# RLB_LTC5510.net
KiCad netlist of a schematic drawn in EAGLE
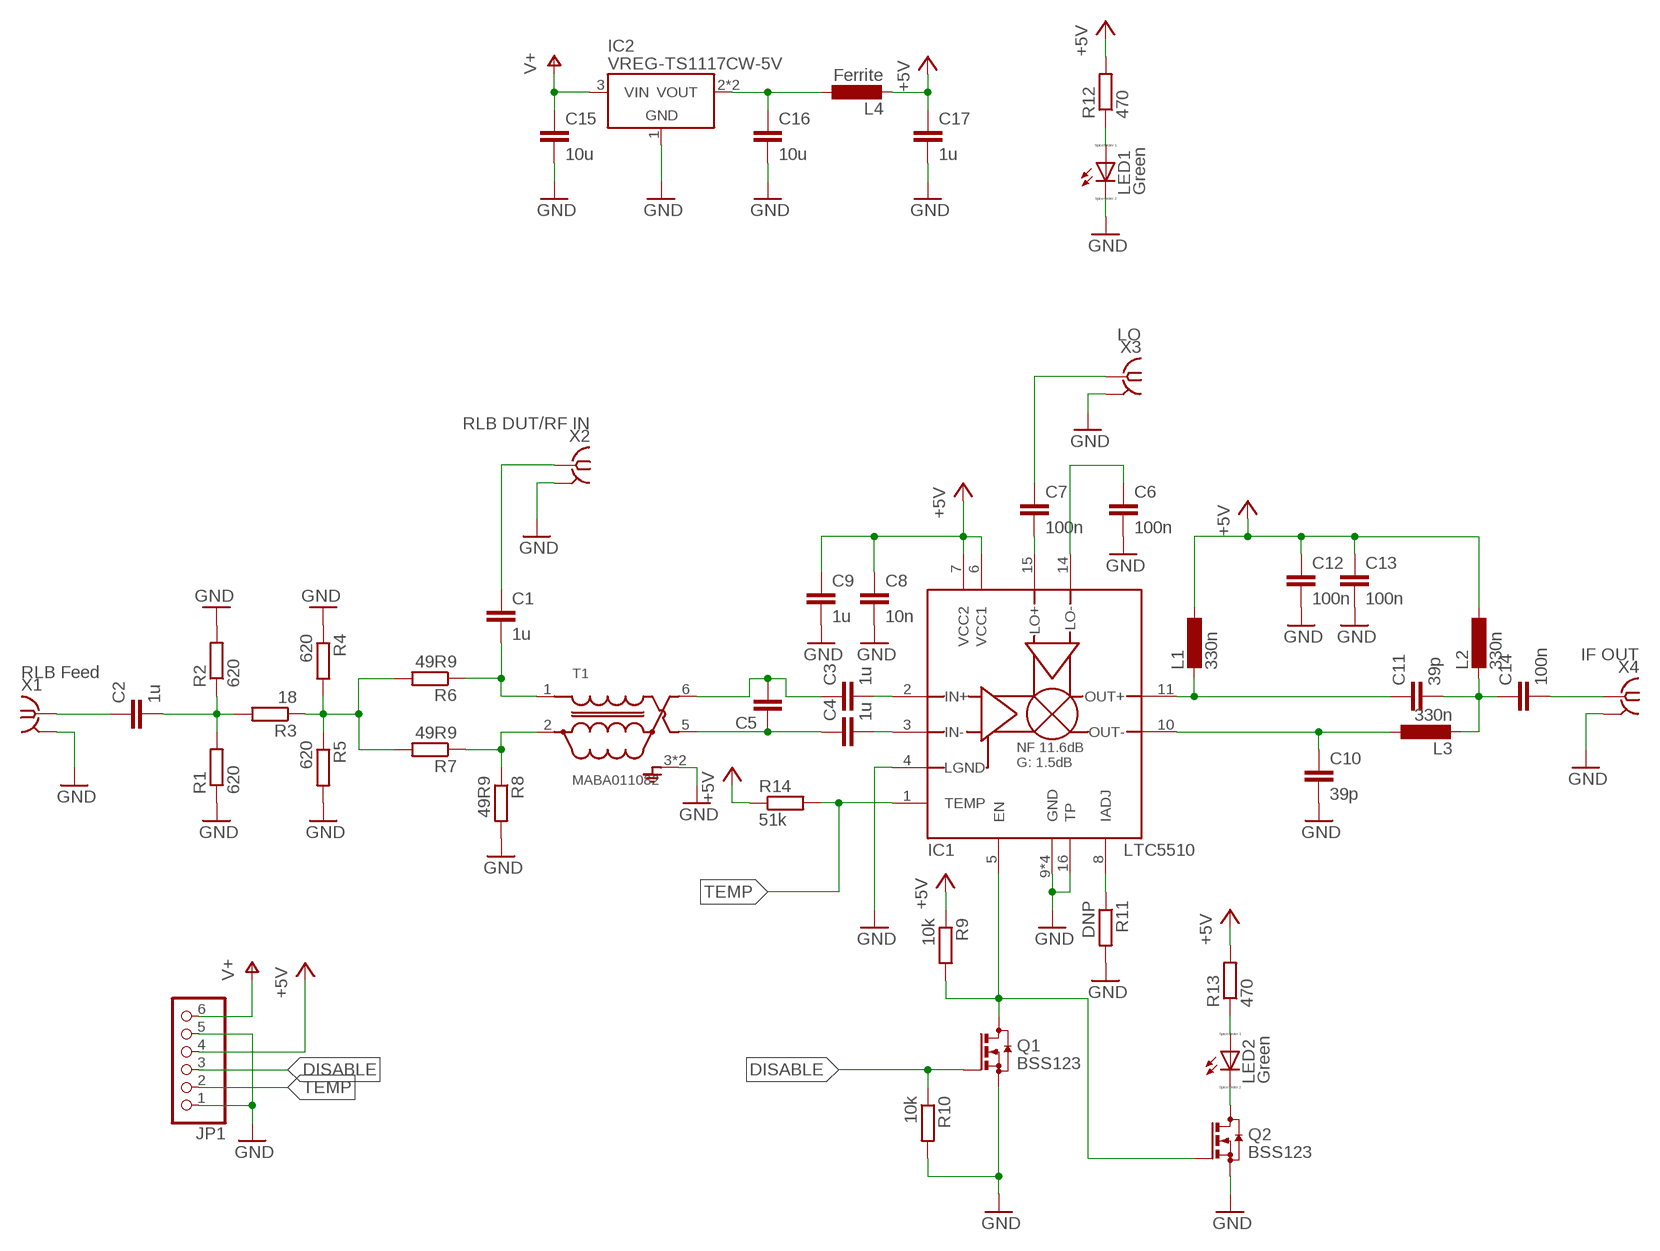
[diagram p0: schematic, sheet 1]

(export (version "E")
  (design (tool "Eeschema 10.0.6"))
  (components
    (comp (ref "C1")
      (value "1u")
      (footprint "eagle-import:C0603")
      (libsource (lib "eagle-import") (part "C-EUC0603"))
    )
    (comp (ref "C2")
      (value "1u")
      (footprint "eagle-import:C0603")
      (libsource (lib "eagle-import") (part "C-EUC0603"))
    )
    (comp (ref "C3")
      (value "1u")
      (footprint "eagle-import:C0603")
      (libsource (lib "eagle-import") (part "C-EUC0603"))
    )
    (comp (ref "C4")
      (value "1u")
      (footprint "eagle-import:C0603")
      (libsource (lib "eagle-import") (part "C-EUC0603"))
    )
    (comp (ref "C5")
      (value "C-EUC0603")
      (footprint "eagle-import:C0603")
      (libsource (lib "eagle-import") (part "C-EUC0603"))
    )
    (comp (ref "C6")
      (value "100n")
      (footprint "eagle-import:C0603")
      (libsource (lib "eagle-import") (part "C-EUC0603"))
    )
    (comp (ref "C7")
      (value "100n")
      (footprint "eagle-import:C0603")
      (libsource (lib "eagle-import") (part "C-EUC0603"))
    )
    (comp (ref "C8")
      (value "10n")
      (footprint "eagle-import:C0603")
      (libsource (lib "eagle-import") (part "C-EUC0603"))
    )
    (comp (ref "C9")
      (value "1u")
      (footprint "eagle-import:C0603")
      (libsource (lib "eagle-import") (part "C-EUC0603"))
    )
    (comp (ref "C10")
      (value "39p")
      (footprint "eagle-import:C0603")
      (libsource (lib "eagle-import") (part "C-EUC0603"))
    )
    (comp (ref "C11")
      (value "39p")
      (footprint "eagle-import:C0603")
      (libsource (lib "eagle-import") (part "C-EUC0603"))
    )
    (comp (ref "C12")
      (value "100n")
      (footprint "eagle-import:C0603")
      (libsource (lib "eagle-import") (part "C-EUC0603"))
    )
    (comp (ref "C13")
      (value "100n")
      (footprint "eagle-import:C0603")
      (libsource (lib "eagle-import") (part "C-EUC0603"))
    )
    (comp (ref "C14")
      (value "100n")
      (footprint "eagle-import:C0603")
      (libsource (lib "eagle-import") (part "C-EUC0603"))
    )
    (comp (ref "C15")
      (value "10u")
      (footprint "eagle-import:C1206")
      (libsource (lib "eagle-import") (part "C-EUC1206"))
    )
    (comp (ref "C16")
      (value "10u")
      (footprint "eagle-import:C1206")
      (libsource (lib "eagle-import") (part "C-EUC1206"))
    )
    (comp (ref "C17")
      (value "1u")
      (footprint "eagle-import:C0603")
      (libsource (lib "eagle-import") (part "C-EUC0603"))
    )
    (comp (ref "IC1")
      (value "LTC5510")
      (footprint "eagle-import:QFN65P400X400X75-17T215N")
      (libsource (lib "eagle-import") (part "LTC5510"))
    )
    (comp (ref "IC2")
      (value "VREG-TS1117CW-5V")
      (footprint "eagle-import:SOT223")
      (libsource (lib "eagle-import") (part "VREG-TS1117CW-5V"))
    )
    (comp (ref "JP1")
      (value "PINHD-1X6/90")
      (footprint "eagle-import:1X06_90")
      (libsource (lib "eagle-import") (part "PINHD-1X6/90"))
    )
    (comp (ref "L1")
      (value "330n")
      (footprint "eagle-import:R0603")
      (libsource (lib "eagle-import") (part "INDUCTOR0603"))
    )
    (comp (ref "L2")
      (value "330n")
      (footprint "eagle-import:R0603")
      (libsource (lib "eagle-import") (part "INDUCTOR0603"))
    )
    (comp (ref "L3")
      (value "330n")
      (footprint "eagle-import:R0603")
      (libsource (lib "eagle-import") (part "INDUCTOR0603"))
    )
    (comp (ref "L4")
      (value "Ferrite")
      (footprint "eagle-import:R0603")
      (libsource (lib "eagle-import") (part "INDUCTOR0603"))
    )
    (comp (ref "LED1")
      (value "Green")
      (footprint "eagle-import:LED_SML0603")
      (libsource (lib "eagle-import") (part "LED_ESML0603"))
    )
    (comp (ref "LED2")
      (value "Green")
      (footprint "eagle-import:LED_SML0603")
      (libsource (lib "eagle-import") (part "LED_ESML0603"))
    )
    (comp (ref "Q1")
      (value "BSS123")
      (footprint "eagle-import:SOT23")
      (libsource (lib "eagle-import") (part "BSS123"))
    )
    (comp (ref "Q2")
      (value "BSS123")
      (footprint "eagle-import:SOT23")
      (libsource (lib "eagle-import") (part "BSS123"))
    )
    (comp (ref "R1")
      (value "620")
      (footprint "eagle-import:R0603")
      (libsource (lib "eagle-import") (part "R-EU_R0603"))
    )
    (comp (ref "R2")
      (value "620")
      (footprint "eagle-import:R0603")
      (libsource (lib "eagle-import") (part "R-EU_R0603"))
    )
    (comp (ref "R3")
      (value "18")
      (footprint "eagle-import:R0603")
      (libsource (lib "eagle-import") (part "R-EU_R0603"))
    )
    (comp (ref "R4")
      (value "620")
      (footprint "eagle-import:R0603")
      (libsource (lib "eagle-import") (part "R-EU_R0603"))
    )
    (comp (ref "R5")
      (value "620")
      (footprint "eagle-import:R0603")
      (libsource (lib "eagle-import") (part "R-EU_R0603"))
    )
    (comp (ref "R6")
      (value "49R9")
      (footprint "eagle-import:R0603")
      (libsource (lib "eagle-import") (part "R-EU_R0603"))
    )
    (comp (ref "R7")
      (value "49R9")
      (footprint "eagle-import:R0603")
      (libsource (lib "eagle-import") (part "R-EU_R0603"))
    )
    (comp (ref "R8")
      (value "49R9")
      (footprint "eagle-import:R0603")
      (libsource (lib "eagle-import") (part "R-EU_R0603"))
    )
    (comp (ref "R9")
      (value "10k")
      (footprint "eagle-import:R0603")
      (libsource (lib "eagle-import") (part "R-EU_R0603"))
    )
    (comp (ref "R10")
      (value "10k")
      (footprint "eagle-import:R0603")
      (libsource (lib "eagle-import") (part "R-EU_R0603"))
    )
    (comp (ref "R11")
      (value "DNP")
      (footprint "eagle-import:R0603")
      (libsource (lib "eagle-import") (part "R-EU_R0603"))
    )
    (comp (ref "R12")
      (value "470")
      (footprint "eagle-import:R0603")
      (libsource (lib "eagle-import") (part "resistor_R-EU_R0603"))
    )
    (comp (ref "R13")
      (value "470")
      (footprint "eagle-import:R0603")
      (libsource (lib "eagle-import") (part "resistor_R-EU_R0603"))
    )
    (comp (ref "R14")
      (value "51k")
      (footprint "eagle-import:R0603")
      (libsource (lib "eagle-import") (part "R-EU_R0603"))
    )
    (comp (ref "T1")
      (value "MABA011082")
      (footprint "eagle-import:MACOM_BALUN")
      (libsource (lib "eagle-import") (part "MABA011082"))
    )
    (comp (ref "X1")
      (value "RLB Feed")
      (footprint "eagle-import:J502-ND-142-0711-821_826")
      (libsource (lib "eagle-import") (part "SMA_CONNECTOR"))
    )
    (comp (ref "X2")
      (value "RLB DUT/RF IN")
      (footprint "eagle-import:J502-ND-142-0711-821_826")
      (libsource (lib "eagle-import") (part "SMA_CONNECTOR"))
    )
    (comp (ref "X3")
      (value "LO")
      (footprint "eagle-import:J502-ND-142-0711-821_826")
      (libsource (lib "eagle-import") (part "SMA_CONNECTOR"))
    )
    (comp (ref "X4")
      (value "IF OUT")
      (footprint "eagle-import:J502-ND-142-0711-821_826")
      (libsource (lib "eagle-import") (part "SMA_CONNECTOR"))
    )
  )
  (nets
    (net (code "1") (name "+5V") (class "Default")
      (node (ref "C12") (pin "1") (pinfunction "1_1") (pintype "passive"))
      (node (ref "C13") (pin "1") (pinfunction "1_1") (pintype "passive"))
      (node (ref "C17") (pin "1") (pinfunction "1_1") (pintype "passive"))
      (node (ref "C8") (pin "1") (pinfunction "1_1") (pintype "passive"))
      (node (ref "C9") (pin "1") (pinfunction "1_1") (pintype "passive"))
      (node (ref "IC1") (pin "6") (pinfunction "VCC1_6") (pintype "bidirectional"))
      (node (ref "IC1") (pin "7") (pinfunction "VCC2_7") (pintype "bidirectional"))
      (node (ref "JP1") (pin "4") (pinfunction "4_4") (pintype "passive"))
      (node (ref "L1") (pin "1") (pinfunction "1_1") (pintype "passive"))
      (node (ref "L2") (pin "1") (pinfunction "1_1") (pintype "passive"))
      (node (ref "L4") (pin "2") (pinfunction "2_2") (pintype "passive"))
      (node (ref "R12") (pin "2") (pinfunction "2_2") (pintype "passive"))
      (node (ref "R13") (pin "2") (pinfunction "2_2") (pintype "passive"))
      (node (ref "R14") (pin "1") (pinfunction "1_1") (pintype "passive"))
      (node (ref "R9") (pin "1") (pinfunction "1_1") (pintype "passive"))
    )
    (net (code "2") (name "DISABLE") (class "Default")
      (node (ref "JP1") (pin "3") (pinfunction "3_3") (pintype "passive"))
      (node (ref "Q1") (pin "1") (pinfunction "G_1") (pintype "passive"))
      (node (ref "R10") (pin "1") (pinfunction "1_1") (pintype "passive"))
    )
    (net (code "3") (name "GND") (class "Default")
      (node (ref "C10") (pin "2") (pinfunction "2_2") (pintype "passive"))
      (node (ref "C12") (pin "2") (pinfunction "2_2") (pintype "passive"))
      (node (ref "C13") (pin "2") (pinfunction "2_2") (pintype "passive"))
      (node (ref "C15") (pin "2") (pinfunction "2_2") (pintype "passive"))
      (node (ref "C16") (pin "2") (pinfunction "2_2") (pintype "passive"))
      (node (ref "C17") (pin "2") (pinfunction "2_2") (pintype "passive"))
      (node (ref "C6") (pin "2") (pinfunction "2_2") (pintype "passive"))
      (node (ref "C8") (pin "2") (pinfunction "2_2") (pintype "passive"))
      (node (ref "C9") (pin "2") (pinfunction "2_2") (pintype "passive"))
      (node (ref "IC1") (pin "12") (pinfunction "GND_12") (pintype "bidirectional"))
      (node (ref "IC1") (pin "13") (pinfunction "GND_13") (pintype "bidirectional"))
      (node (ref "IC1") (pin "16") (pinfunction "TP_16") (pintype "bidirectional"))
      (node (ref "IC1") (pin "17") (pinfunction "GND_17") (pintype "bidirectional"))
      (node (ref "IC1") (pin "4") (pinfunction "LGND_4") (pintype "bidirectional"))
      (node (ref "IC1") (pin "9") (pinfunction "GND_9") (pintype "bidirectional"))
      (node (ref "IC2") (pin "1") (pinfunction "GND_1") (pintype "power_in"))
      (node (ref "JP1") (pin "1") (pinfunction "1_1") (pintype "passive"))
      (node (ref "JP1") (pin "5") (pinfunction "5_5") (pintype "passive"))
      (node (ref "LED1") (pin "C") (pinfunction "C_C") (pintype "passive"))
      (node (ref "Q1") (pin "2") (pinfunction "S_2") (pintype "passive"))
      (node (ref "Q2") (pin "2") (pinfunction "S_2") (pintype "passive"))
      (node (ref "R1") (pin "1") (pinfunction "1_1") (pintype "passive"))
      (node (ref "R10") (pin "2") (pinfunction "2_2") (pintype "passive"))
      (node (ref "R11") (pin "2") (pinfunction "2_2") (pintype "passive"))
      (node (ref "R2") (pin "2") (pinfunction "2_2") (pintype "passive"))
      (node (ref "R4") (pin "1") (pinfunction "1_1") (pintype "passive"))
      (node (ref "R5") (pin "2") (pinfunction "2_2") (pintype "passive"))
      (node (ref "R8") (pin "2") (pinfunction "2_2") (pintype "passive"))
      (node (ref "T1") (pin "3") (pinfunction "GND_3") (pintype "bidirectional"))
      (node (ref "T1") (pin "4") (pinfunction "GND_4") (pintype "bidirectional"))
      (node (ref "X1") (pin "G@1") (pinfunction "2_G@1") (pintype "passive"))
      (node (ref "X1") (pin "G@2") (pinfunction "2_G@2") (pintype "passive"))
      (node (ref "X1") (pin "G@3") (pinfunction "2_G@3") (pintype "passive"))
      (node (ref "X1") (pin "G@4") (pinfunction "2_G@4") (pintype "passive"))
      (node (ref "X2") (pin "G@1") (pinfunction "2_G@1") (pintype "passive"))
      (node (ref "X2") (pin "G@2") (pinfunction "2_G@2") (pintype "passive"))
      (node (ref "X2") (pin "G@3") (pinfunction "2_G@3") (pintype "passive"))
      (node (ref "X2") (pin "G@4") (pinfunction "2_G@4") (pintype "passive"))
      (node (ref "X3") (pin "G@1") (pinfunction "2_G@1") (pintype "passive"))
      (node (ref "X3") (pin "G@2") (pinfunction "2_G@2") (pintype "passive"))
      (node (ref "X3") (pin "G@3") (pinfunction "2_G@3") (pintype "passive"))
      (node (ref "X3") (pin "G@4") (pinfunction "2_G@4") (pintype "passive"))
      (node (ref "X4") (pin "G@1") (pinfunction "2_G@1") (pintype "passive"))
      (node (ref "X4") (pin "G@2") (pinfunction "2_G@2") (pintype "passive"))
      (node (ref "X4") (pin "G@3") (pinfunction "2_G@3") (pintype "passive"))
      (node (ref "X4") (pin "G@4") (pinfunction "2_G@4") (pintype "passive"))
    )
    (net (code "4") (name "Net-(C1-Pad1)") (class "Default")
      (node (ref "C1") (pin "1") (pinfunction "1_1") (pintype "passive"))
      (node (ref "X2") (pin "1") (pinfunction "1_1") (pintype "passive"))
    )
    (net (code "5") (name "Net-(C2-Pad1)") (class "Default")
      (node (ref "C2") (pin "1") (pinfunction "1_1") (pintype "passive"))
      (node (ref "X1") (pin "1") (pinfunction "1_1") (pintype "passive"))
    )
    (net (code "6") (name "Net-(C2-Pad2)") (class "Default")
      (node (ref "C2") (pin "2") (pinfunction "2_2") (pintype "passive"))
      (node (ref "R1") (pin "2") (pinfunction "2_2") (pintype "passive"))
      (node (ref "R2") (pin "1") (pinfunction "1_1") (pintype "passive"))
      (node (ref "R3") (pin "2") (pinfunction "2_2") (pintype "passive"))
    )
    (net (code "7") (name "Net-(C7-Pad1)") (class "Default")
      (node (ref "C7") (pin "1") (pinfunction "1_1") (pintype "passive"))
      (node (ref "X3") (pin "1") (pinfunction "1_1") (pintype "passive"))
    )
    (net (code "8") (name "Net-(C11-Pad2)") (class "Default")
      (node (ref "C11") (pin "2") (pinfunction "2_2") (pintype "passive"))
      (node (ref "C14") (pin "1") (pinfunction "1_1") (pintype "passive"))
      (node (ref "L2") (pin "2") (pinfunction "2_2") (pintype "passive"))
      (node (ref "L3") (pin "2") (pinfunction "2_2") (pintype "passive"))
    )
    (net (code "9") (name "Net-(C14-Pad2)") (class "Default")
      (node (ref "C14") (pin "2") (pinfunction "2_2") (pintype "passive"))
      (node (ref "X4") (pin "1") (pinfunction "1_1") (pintype "passive"))
    )
    (net (code "10") (name "Net-(C16-Pad1)") (class "Default")
      (node (ref "C16") (pin "1") (pinfunction "1_1") (pintype "passive"))
      (node (ref "IC2") (pin "2") (pinfunction "VOUT_2") (pintype "power_in"))
      (node (ref "IC2") (pin "4") (pinfunction "VOUT_4") (pintype "power_in"))
      (node (ref "L4") (pin "1") (pinfunction "1_1") (pintype "passive"))
    )
    (net (code "11") (name "Net-(IC1-EN)") (class "Default")
      (node (ref "IC1") (pin "5") (pinfunction "EN_5") (pintype "bidirectional"))
      (node (ref "Q1") (pin "3") (pinfunction "D_3") (pintype "passive"))
      (node (ref "Q2") (pin "1") (pinfunction "G_1") (pintype "passive"))
      (node (ref "R9") (pin "2") (pinfunction "2_2") (pintype "passive"))
    )
    (net (code "12") (name "Net-(IC1-IADJ)") (class "Default")
      (node (ref "IC1") (pin "8") (pinfunction "IADJ_8") (pintype "bidirectional"))
      (node (ref "R11") (pin "1") (pinfunction "1_1") (pintype "passive"))
    )
    (net (code "13") (name "Net-(IC1-IN+)") (class "Default")
      (node (ref "C3") (pin "2") (pinfunction "2_2") (pintype "passive"))
      (node (ref "IC1") (pin "2") (pinfunction "IN+_2") (pintype "bidirectional"))
    )
    (net (code "14") (name "Net-(IC1-IN-)") (class "Default")
      (node (ref "C4") (pin "2") (pinfunction "2_2") (pintype "passive"))
      (node (ref "IC1") (pin "3") (pinfunction "IN-_3") (pintype "bidirectional"))
    )
    (net (code "15") (name "Net-(IC1-LO+)") (class "Default")
      (node (ref "C7") (pin "2") (pinfunction "2_2") (pintype "passive"))
      (node (ref "IC1") (pin "15") (pinfunction "LO+_15") (pintype "bidirectional"))
    )
    (net (code "16") (name "Net-(IC1-LO-)") (class "Default")
      (node (ref "C6") (pin "1") (pinfunction "1_1") (pintype "passive"))
      (node (ref "IC1") (pin "14") (pinfunction "LO-_14") (pintype "bidirectional"))
    )
    (net (code "17") (name "Net-(IC1-OUT+)") (class "Default")
      (node (ref "C11") (pin "1") (pinfunction "1_1") (pintype "passive"))
      (node (ref "IC1") (pin "11") (pinfunction "OUT+_11") (pintype "bidirectional"))
      (node (ref "L1") (pin "2") (pinfunction "2_2") (pintype "passive"))
    )
    (net (code "18") (name "Net-(IC1-OUT-)") (class "Default")
      (node (ref "C10") (pin "1") (pinfunction "1_1") (pintype "passive"))
      (node (ref "IC1") (pin "10") (pinfunction "OUT-_10") (pintype "bidirectional"))
      (node (ref "L3") (pin "1") (pinfunction "1_1") (pintype "passive"))
    )
    (net (code "19") (name "Net-(LED1-PadA)") (class "Default")
      (node (ref "LED1") (pin "A") (pinfunction "A_A") (pintype "passive"))
      (node (ref "R12") (pin "1") (pinfunction "1_1") (pintype "passive"))
    )
    (net (code "20") (name "Net-(LED2-PadA)") (class "Default")
      (node (ref "LED2") (pin "A") (pinfunction "A_A") (pintype "passive"))
      (node (ref "R13") (pin "1") (pinfunction "1_1") (pintype "passive"))
    )
    (net (code "21") (name "Net-(Q2-D)") (class "Default")
      (node (ref "LED2") (pin "C") (pinfunction "C_C") (pintype "passive"))
      (node (ref "Q2") (pin "3") (pinfunction "D_3") (pintype "passive"))
    )
    (net (code "22") (name "Net-(R3-Pad1)") (class "Default")
      (node (ref "R3") (pin "1") (pinfunction "1_1") (pintype "passive"))
      (node (ref "R4") (pin "2") (pinfunction "2_2") (pintype "passive"))
      (node (ref "R5") (pin "1") (pinfunction "1_1") (pintype "passive"))
      (node (ref "R6") (pin "2") (pinfunction "2_2") (pintype "passive"))
      (node (ref "R7") (pin "2") (pinfunction "2_2") (pintype "passive"))
    )
    (net (code "23") (name "Net-(T1-PIN1)") (class "Default")
      (node (ref "C1") (pin "2") (pinfunction "2_2") (pintype "passive"))
      (node (ref "R6") (pin "1") (pinfunction "1_1") (pintype "passive"))
      (node (ref "T1") (pin "1") (pinfunction "PIN1_1") (pintype "bidirectional"))
    )
    (net (code "24") (name "Net-(T1-PIN2)") (class "Default")
      (node (ref "R7") (pin "1") (pinfunction "1_1") (pintype "passive"))
      (node (ref "R8") (pin "1") (pinfunction "1_1") (pintype "passive"))
      (node (ref "T1") (pin "2") (pinfunction "PIN2_2") (pintype "bidirectional"))
    )
    (net (code "25") (name "Net-(T1-PIN5)") (class "Default")
      (node (ref "C4") (pin "1") (pinfunction "1_1") (pintype "passive"))
      (node (ref "C5") (pin "1") (pinfunction "1_1") (pintype "passive"))
      (node (ref "T1") (pin "5") (pinfunction "PIN5_5") (pintype "bidirectional"))
    )
    (net (code "26") (name "Net-(T1-PIN6)") (class "Default")
      (node (ref "C3") (pin "1") (pinfunction "1_1") (pintype "passive"))
      (node (ref "C5") (pin "2") (pinfunction "2_2") (pintype "passive"))
      (node (ref "T1") (pin "6") (pinfunction "PIN6_6") (pintype "bidirectional"))
    )
    (net (code "27") (name "TEMP") (class "Default")
      (node (ref "IC1") (pin "1") (pinfunction "TEMP_1") (pintype "bidirectional"))
      (node (ref "JP1") (pin "2") (pinfunction "2_2") (pintype "passive"))
      (node (ref "R14") (pin "2") (pinfunction "2_2") (pintype "passive"))
    )
    (net (code "28") (name "V+") (class "Default")
      (node (ref "C15") (pin "1") (pinfunction "1_1") (pintype "passive"))
      (node (ref "IC2") (pin "3") (pinfunction "VIN_3") (pintype "power_in"))
      (node (ref "JP1") (pin "6") (pinfunction "6_6") (pintype "passive"))
    )
  )
)
